# MW-Mega-Shield.net
KiCad netlist of a schematic drawn in EAGLE
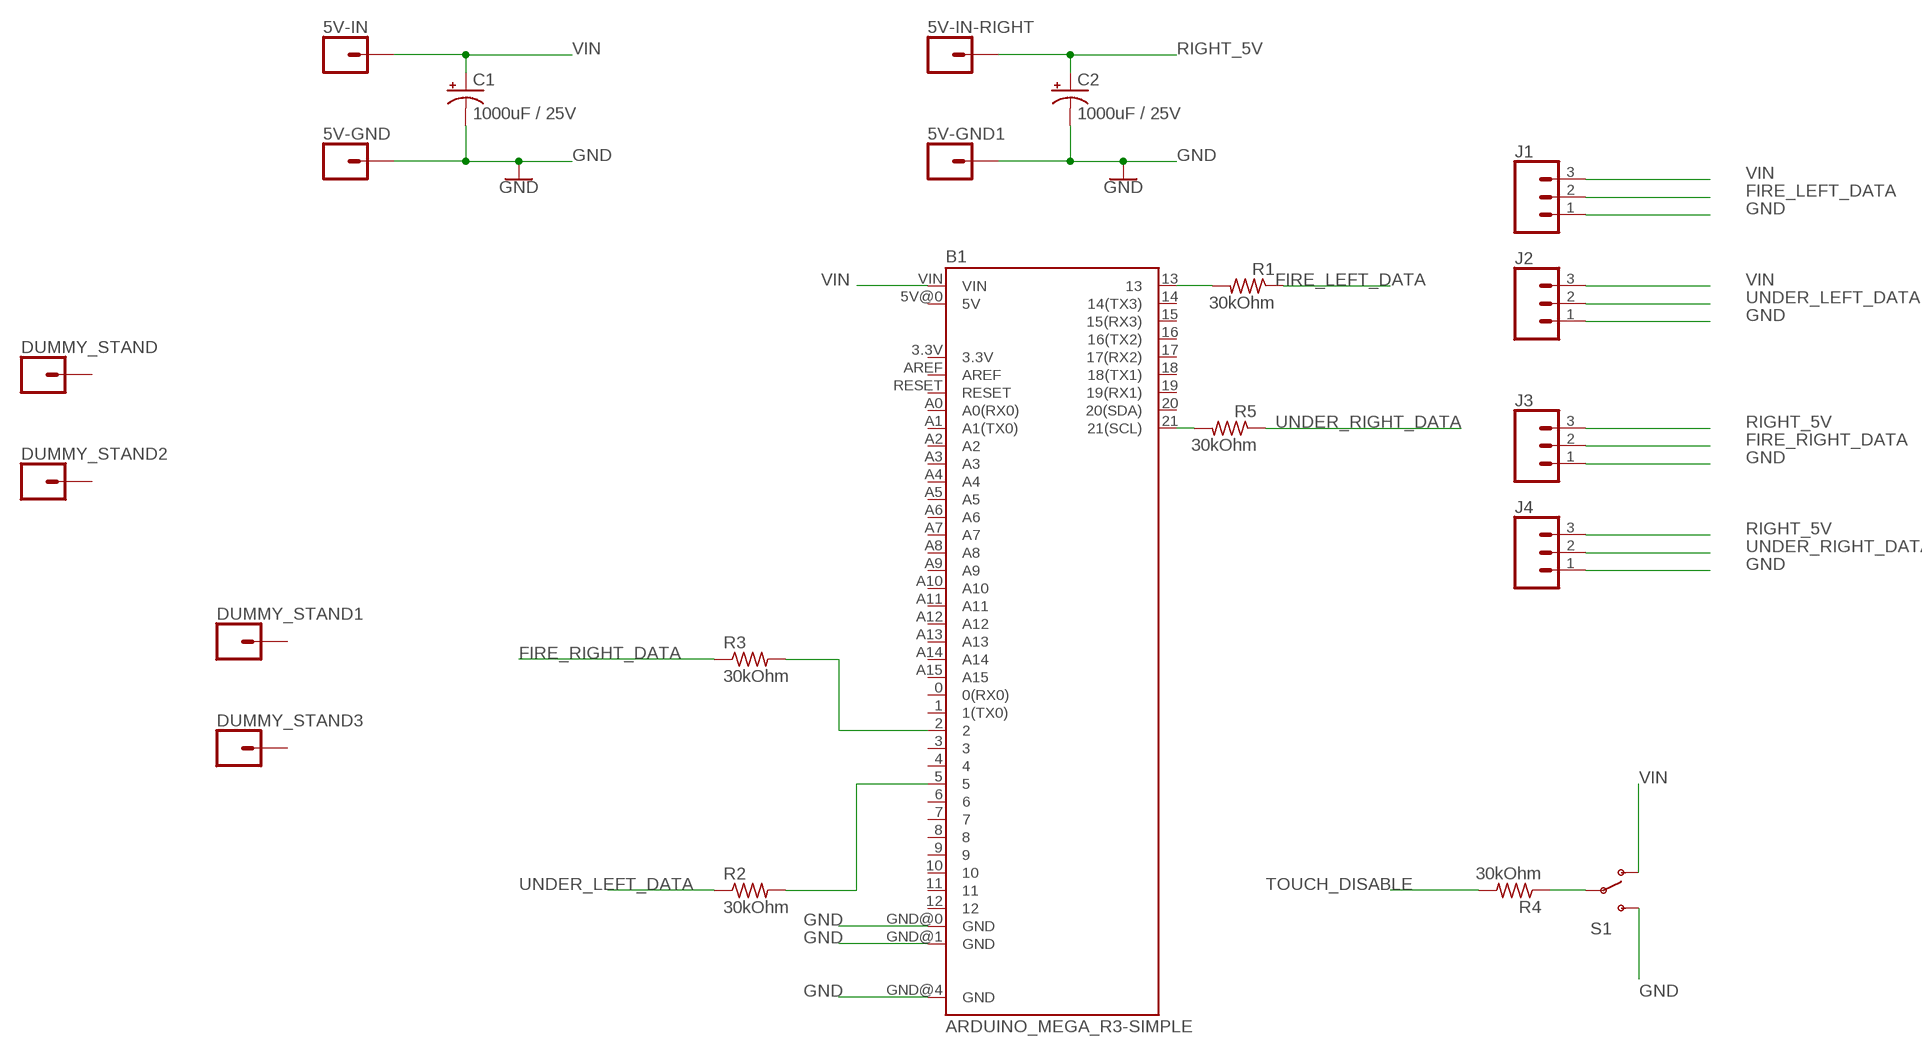
[diagram p0: schematic, sheet 1]

(export (version "E")
  (design (tool "Eeschema 10.0.6"))
  (components
    (comp (ref "5V-GND")
      (value "CONN_01")
      (footprint "eagle-import:1X01")
      (libsource (lib "eagle-import") (part "CONN_01"))
    )
    (comp (ref "5V-GND1")
      (value "CONN_01")
      (footprint "eagle-import:1X01")
      (libsource (lib "eagle-import") (part "CONN_01"))
    )
    (comp (ref "5V-IN")
      (value "CONN_01")
      (footprint "eagle-import:1X01")
      (libsource (lib "eagle-import") (part "CONN_01"))
    )
    (comp (ref "5V-IN-RIGHT")
      (value "CONN_01")
      (footprint "eagle-import:1X01")
      (libsource (lib "eagle-import") (part "CONN_01"))
    )
    (comp (ref "B1")
      (value "ARDUINO_MEGA_R3-SIMPLE")
      (footprint "eagle-import:ARDUINO_MEGA-SIMPLE_SHIELD")
      (libsource (lib "eagle-import") (part "ARDUINO_MEGA_R3-SIMPLE"))
    )
    (comp (ref "C1")
      (value "1000uF / 25V")
      (footprint "eagle-import:E5-10,5")
      (libsource (lib "eagle-import") (part "CPOL-USE5-10.5"))
    )
    (comp (ref "C2")
      (value "1000uF / 25V")
      (footprint "eagle-import:E5-10,5")
      (libsource (lib "eagle-import") (part "CPOL-USE5-10.5"))
    )
    (comp (ref "DUMMY_STAND")
      (value "CONN_01")
      (footprint "eagle-import:1X01")
      (libsource (lib "eagle-import") (part "CONN_01"))
    )
    (comp (ref "DUMMY_STAND1")
      (value "CONN_01")
      (footprint "eagle-import:1X01")
      (libsource (lib "eagle-import") (part "CONN_01"))
    )
    (comp (ref "DUMMY_STAND2")
      (value "CONN_01")
      (footprint "eagle-import:1X01")
      (libsource (lib "eagle-import") (part "CONN_01"))
    )
    (comp (ref "DUMMY_STAND3")
      (value "CONN_01")
      (footprint "eagle-import:1X01")
      (libsource (lib "eagle-import") (part "CONN_01"))
    )
    (comp (ref "J1")
      (value "CONN_03SCREW-NS")
      (footprint "eagle-import:SCREWTERMINAL-3.5MM-3-NS")
      (libsource (lib "eagle-import") (part "CONN_03SCREW-NS"))
    )
    (comp (ref "J2")
      (value "CONN_03SCREW-NS")
      (footprint "eagle-import:SCREWTERMINAL-3.5MM-3-NS")
      (libsource (lib "eagle-import") (part "CONN_03SCREW-NS"))
    )
    (comp (ref "J3")
      (value "CONN_03SCREW-NS")
      (footprint "eagle-import:SCREWTERMINAL-3.5MM-3-NS")
      (libsource (lib "eagle-import") (part "CONN_03SCREW-NS"))
    )
    (comp (ref "J4")
      (value "CONN_03SCREW-NS")
      (footprint "eagle-import:SCREWTERMINAL-3.5MM-3-NS")
      (libsource (lib "eagle-import") (part "CONN_03SCREW-NS"))
    )
    (comp (ref "R1")
      (value "30kOhm")
      (footprint "eagle-import:R0603")
      (libsource (lib "eagle-import") (part "R-US_R0603"))
    )
    (comp (ref "R2")
      (value "30kOhm")
      (footprint "eagle-import:R0603")
      (libsource (lib "eagle-import") (part "R-US_R0603"))
    )
    (comp (ref "R3")
      (value "30kOhm")
      (footprint "eagle-import:R0603")
      (libsource (lib "eagle-import") (part "R-US_R0603"))
    )
    (comp (ref "R4")
      (value "30kOhm")
      (footprint "eagle-import:R0603")
      (libsource (lib "eagle-import") (part "R-US_R0603"))
    )
    (comp (ref "R5")
      (value "30kOhm")
      (footprint "eagle-import:R0603")
      (libsource (lib "eagle-import") (part "R-US_R0603"))
    )
    (comp (ref "S1")
      (value "SWITCH-SPDTSMD")
      (footprint "eagle-import:SWITCH_SPDT_SMD")
      (libsource (lib "eagle-import") (part "SWITCH-SPDTSMD"))
    )
  )
  (nets
    (net (code "1") (name "/FIRE_LEFT_DATA") (class "Default")
      (node (ref "J1") (pin "2") (pinfunction "2_2") (pintype "passive"))
      (node (ref "R1") (pin "1") (pinfunction "1_1") (pintype "passive"))
    )
    (net (code "2") (name "/FIRE_RIGHT_DATA") (class "Default")
      (node (ref "J3") (pin "2") (pinfunction "2_2") (pintype "passive"))
      (node (ref "R3") (pin "1") (pinfunction "1_1") (pintype "passive"))
    )
    (net (code "3") (name "/RIGHT_5V") (class "Default")
      (node (ref "5V-IN-RIGHT") (pin "1") (pinfunction "1_1") (pintype "passive"))
      (node (ref "C2") (pin "+") (pinfunction "+_+") (pintype "passive"))
      (node (ref "J3") (pin "3") (pinfunction "3_3") (pintype "passive"))
      (node (ref "J4") (pin "3") (pinfunction "3_3") (pintype "passive"))
    )
    (net (code "4") (name "/TOUCH_DISABLE") (class "Default")
      (node (ref "R4") (pin "2") (pinfunction "2_2") (pintype "passive"))
    )
    (net (code "5") (name "/UNDER_LEFT_DATA") (class "Default")
      (node (ref "J2") (pin "2") (pinfunction "2_2") (pintype "passive"))
      (node (ref "R2") (pin "1") (pinfunction "1_1") (pintype "passive"))
    )
    (net (code "6") (name "/UNDER_RIGHT_DATA") (class "Default")
      (node (ref "J4") (pin "2") (pinfunction "2_2") (pintype "passive"))
      (node (ref "R5") (pin "1") (pinfunction "1_1") (pintype "passive"))
    )
    (net (code "7") (name "/VIN") (class "Default")
      (node (ref "5V-IN") (pin "1") (pinfunction "1_1") (pintype "passive"))
      (node (ref "B1") (pin "VIN") (pinfunction "VIN_VIN") (pintype "bidirectional"))
      (node (ref "C1") (pin "+") (pinfunction "+_+") (pintype "passive"))
      (node (ref "J1") (pin "3") (pinfunction "3_3") (pintype "passive"))
      (node (ref "J2") (pin "3") (pinfunction "3_3") (pintype "passive"))
      (node (ref "S1") (pin "1") (pinfunction "O_1") (pintype "passive"))
    )
    (net (code "8") (name "GND") (class "Default")
      (node (ref "5V-GND") (pin "1") (pinfunction "1_1") (pintype "passive"))
      (node (ref "5V-GND1") (pin "1") (pinfunction "1_1") (pintype "passive"))
      (node (ref "B1") (pin "GND@0") (pinfunction "GND_GND@0") (pintype "bidirectional"))
      (node (ref "B1") (pin "GND@1") (pinfunction "GND_GND@1") (pintype "bidirectional"))
      (node (ref "B1") (pin "GND@4") (pinfunction "GND_GND@4") (pintype "bidirectional"))
      (node (ref "C1") (pin "-") (pinfunction "-_-") (pintype "passive"))
      (node (ref "C2") (pin "-") (pinfunction "-_-") (pintype "passive"))
      (node (ref "J1") (pin "1") (pinfunction "1_1") (pintype "passive"))
      (node (ref "J2") (pin "1") (pinfunction "1_1") (pintype "passive"))
      (node (ref "J3") (pin "1") (pinfunction "1_1") (pintype "passive"))
      (node (ref "J4") (pin "1") (pinfunction "1_1") (pintype "passive"))
      (node (ref "S1") (pin "3") (pinfunction "S_3") (pintype "passive"))
    )
    (net (code "9") (name "Net-(B1-21(SCL))") (class "Default")
      (node (ref "B1") (pin "21") (pinfunction "21(SCL)_21") (pintype "bidirectional"))
      (node (ref "R5") (pin "2") (pinfunction "2_2") (pintype "passive"))
    )
    (net (code "10") (name "Net-(B1-Pad2)") (class "Default")
      (node (ref "B1") (pin "2") (pinfunction "2_2") (pintype "bidirectional"))
      (node (ref "R3") (pin "2") (pinfunction "2_2") (pintype "passive"))
    )
    (net (code "11") (name "Net-(B1-Pad5)") (class "Default")
      (node (ref "B1") (pin "5") (pinfunction "5_5") (pintype "bidirectional"))
      (node (ref "R2") (pin "2") (pinfunction "2_2") (pintype "passive"))
    )
    (net (code "12") (name "Net-(B1-Pad13)") (class "Default")
      (node (ref "B1") (pin "13") (pinfunction "13_13") (pintype "bidirectional"))
      (node (ref "R1") (pin "2") (pinfunction "2_2") (pintype "passive"))
    )
    (net (code "13") (name "Net-(S1-P)") (class "Default")
      (node (ref "R4") (pin "1") (pinfunction "1_1") (pintype "passive"))
      (node (ref "S1") (pin "2") (pinfunction "P_2") (pintype "passive"))
    )
    (net (code "14") (name "unconnected-(B1-0(RX0)-Pad0)") (class "Default")
      (node (ref "B1") (pin "0") (pinfunction "0(RX0)_0") (pintype "bidirectional"))
    )
    (net (code "15") (name "unconnected-(B1-1(TX0)-Pad1)") (class "Default")
      (node (ref "B1") (pin "1") (pinfunction "1(TX0)_1") (pintype "bidirectional"))
    )
    (net (code "16") (name "unconnected-(B1-5V-Pad5V@0)") (class "Default")
      (node (ref "B1") (pin "5V@0") (pinfunction "5V_5V@0") (pintype "bidirectional"))
    )
    (net (code "17") (name "unconnected-(B1-14(TX3)-Pad14)") (class "Default")
      (node (ref "B1") (pin "14") (pinfunction "14(TX3)_14") (pintype "bidirectional"))
    )
    (net (code "18") (name "unconnected-(B1-15(RX3)-Pad15)") (class "Default")
      (node (ref "B1") (pin "15") (pinfunction "15(RX3)_15") (pintype "bidirectional"))
    )
    (net (code "19") (name "unconnected-(B1-16(TX2)-Pad16)") (class "Default")
      (node (ref "B1") (pin "16") (pinfunction "16(TX2)_16") (pintype "bidirectional"))
    )
    (net (code "20") (name "unconnected-(B1-17(RX2)-Pad17)") (class "Default")
      (node (ref "B1") (pin "17") (pinfunction "17(RX2)_17") (pintype "bidirectional"))
    )
    (net (code "21") (name "unconnected-(B1-18(TX1)-Pad18)") (class "Default")
      (node (ref "B1") (pin "18") (pinfunction "18(TX1)_18") (pintype "bidirectional"))
    )
    (net (code "22") (name "unconnected-(B1-19(RX1)-Pad19)") (class "Default")
      (node (ref "B1") (pin "19") (pinfunction "19(RX1)_19") (pintype "bidirectional"))
    )
    (net (code "23") (name "unconnected-(B1-20(SDA)-Pad20)") (class "Default")
      (node (ref "B1") (pin "20") (pinfunction "20(SDA)_20") (pintype "bidirectional"))
    )
    (net (code "24") (name "unconnected-(B1-A0(RX0)-PadA0)") (class "Default")
      (node (ref "B1") (pin "A0") (pinfunction "A0(RX0)_A0") (pintype "bidirectional"))
    )
    (net (code "25") (name "unconnected-(B1-A1(TX0)-PadA1)") (class "Default")
      (node (ref "B1") (pin "A1") (pinfunction "A1(TX0)_A1") (pintype "bidirectional"))
    )
    (net (code "26") (name "unconnected-(B1-Pad3)") (class "Default")
      (node (ref "B1") (pin "3") (pinfunction "3_3") (pintype "bidirectional"))
    )
    (net (code "27") (name "unconnected-(B1-Pad3.3V)") (class "Default")
      (node (ref "B1") (pin "3.3V") (pinfunction "3.3V_3.3V") (pintype "bidirectional"))
    )
    (net (code "28") (name "unconnected-(B1-Pad4)") (class "Default")
      (node (ref "B1") (pin "4") (pinfunction "4_4") (pintype "bidirectional"))
    )
    (net (code "29") (name "unconnected-(B1-Pad6)") (class "Default")
      (node (ref "B1") (pin "6") (pinfunction "6_6") (pintype "bidirectional"))
    )
    (net (code "30") (name "unconnected-(B1-Pad7)") (class "Default")
      (node (ref "B1") (pin "7") (pinfunction "7_7") (pintype "bidirectional"))
    )
    (net (code "31") (name "unconnected-(B1-Pad8)") (class "Default")
      (node (ref "B1") (pin "8") (pinfunction "8_8") (pintype "bidirectional"))
    )
    (net (code "32") (name "unconnected-(B1-Pad9)") (class "Default")
      (node (ref "B1") (pin "9") (pinfunction "9_9") (pintype "bidirectional"))
    )
    (net (code "33") (name "unconnected-(B1-Pad10)") (class "Default")
      (node (ref "B1") (pin "10") (pinfunction "10_10") (pintype "bidirectional"))
    )
    (net (code "34") (name "unconnected-(B1-Pad11)") (class "Default")
      (node (ref "B1") (pin "11") (pinfunction "11_11") (pintype "bidirectional"))
    )
    (net (code "35") (name "unconnected-(B1-Pad12)") (class "Default")
      (node (ref "B1") (pin "12") (pinfunction "12_12") (pintype "bidirectional"))
    )
    (net (code "36") (name "unconnected-(B1-PadA2)") (class "Default")
      (node (ref "B1") (pin "A2") (pinfunction "A2_A2") (pintype "bidirectional"))
    )
    (net (code "37") (name "unconnected-(B1-PadA3)") (class "Default")
      (node (ref "B1") (pin "A3") (pinfunction "A3_A3") (pintype "bidirectional"))
    )
    (net (code "38") (name "unconnected-(B1-PadA4)") (class "Default")
      (node (ref "B1") (pin "A4") (pinfunction "A4_A4") (pintype "bidirectional"))
    )
    (net (code "39") (name "unconnected-(B1-PadA5)") (class "Default")
      (node (ref "B1") (pin "A5") (pinfunction "A5_A5") (pintype "bidirectional"))
    )
    (net (code "40") (name "unconnected-(B1-PadA6)") (class "Default")
      (node (ref "B1") (pin "A6") (pinfunction "A6_A6") (pintype "bidirectional"))
    )
    (net (code "41") (name "unconnected-(B1-PadA7)") (class "Default")
      (node (ref "B1") (pin "A7") (pinfunction "A7_A7") (pintype "bidirectional"))
    )
    (net (code "42") (name "unconnected-(B1-PadA8)") (class "Default")
      (node (ref "B1") (pin "A8") (pinfunction "A8_A8") (pintype "bidirectional"))
    )
    (net (code "43") (name "unconnected-(B1-PadA9)") (class "Default")
      (node (ref "B1") (pin "A9") (pinfunction "A9_A9") (pintype "bidirectional"))
    )
    (net (code "44") (name "unconnected-(B1-PadA10)") (class "Default")
      (node (ref "B1") (pin "A10") (pinfunction "A10_A10") (pintype "bidirectional"))
    )
    (net (code "45") (name "unconnected-(B1-PadA11)") (class "Default")
      (node (ref "B1") (pin "A11") (pinfunction "A11_A11") (pintype "bidirectional"))
    )
    (net (code "46") (name "unconnected-(B1-PadA12)") (class "Default")
      (node (ref "B1") (pin "A12") (pinfunction "A12_A12") (pintype "bidirectional"))
    )
    (net (code "47") (name "unconnected-(B1-PadA13)") (class "Default")
      (node (ref "B1") (pin "A13") (pinfunction "A13_A13") (pintype "bidirectional"))
    )
    (net (code "48") (name "unconnected-(B1-PadA14)") (class "Default")
      (node (ref "B1") (pin "A14") (pinfunction "A14_A14") (pintype "bidirectional"))
    )
    (net (code "49") (name "unconnected-(B1-PadA15)") (class "Default")
      (node (ref "B1") (pin "A15") (pinfunction "A15_A15") (pintype "bidirectional"))
    )
    (net (code "50") (name "unconnected-(B1-PadAREF)") (class "Default")
      (node (ref "B1") (pin "AREF") (pinfunction "AREF_AREF") (pintype "bidirectional"))
    )
    (net (code "51") (name "unconnected-(B1-PadRESET)") (class "Default")
      (node (ref "B1") (pin "RESET") (pinfunction "RESET_RESET") (pintype "bidirectional"))
    )
    (net (code "52") (name "unconnected-(DUMMY_STAND-Pad1)") (class "Default")
      (node (ref "DUMMY_STAND") (pin "1") (pinfunction "1_1") (pintype "passive"))
    )
    (net (code "53") (name "unconnected-(DUMMY_STAND1-Pad1)") (class "Default")
      (node (ref "DUMMY_STAND1") (pin "1") (pinfunction "1_1") (pintype "passive"))
    )
    (net (code "54") (name "unconnected-(DUMMY_STAND2-Pad1)") (class "Default")
      (node (ref "DUMMY_STAND2") (pin "1") (pinfunction "1_1") (pintype "passive"))
    )
    (net (code "55") (name "unconnected-(DUMMY_STAND3-Pad1)") (class "Default")
      (node (ref "DUMMY_STAND3") (pin "1") (pinfunction "1_1") (pintype "passive"))
    )
  )
)
